# IDL.net
KiCad netlist of a schematic drawn in Altium Designer
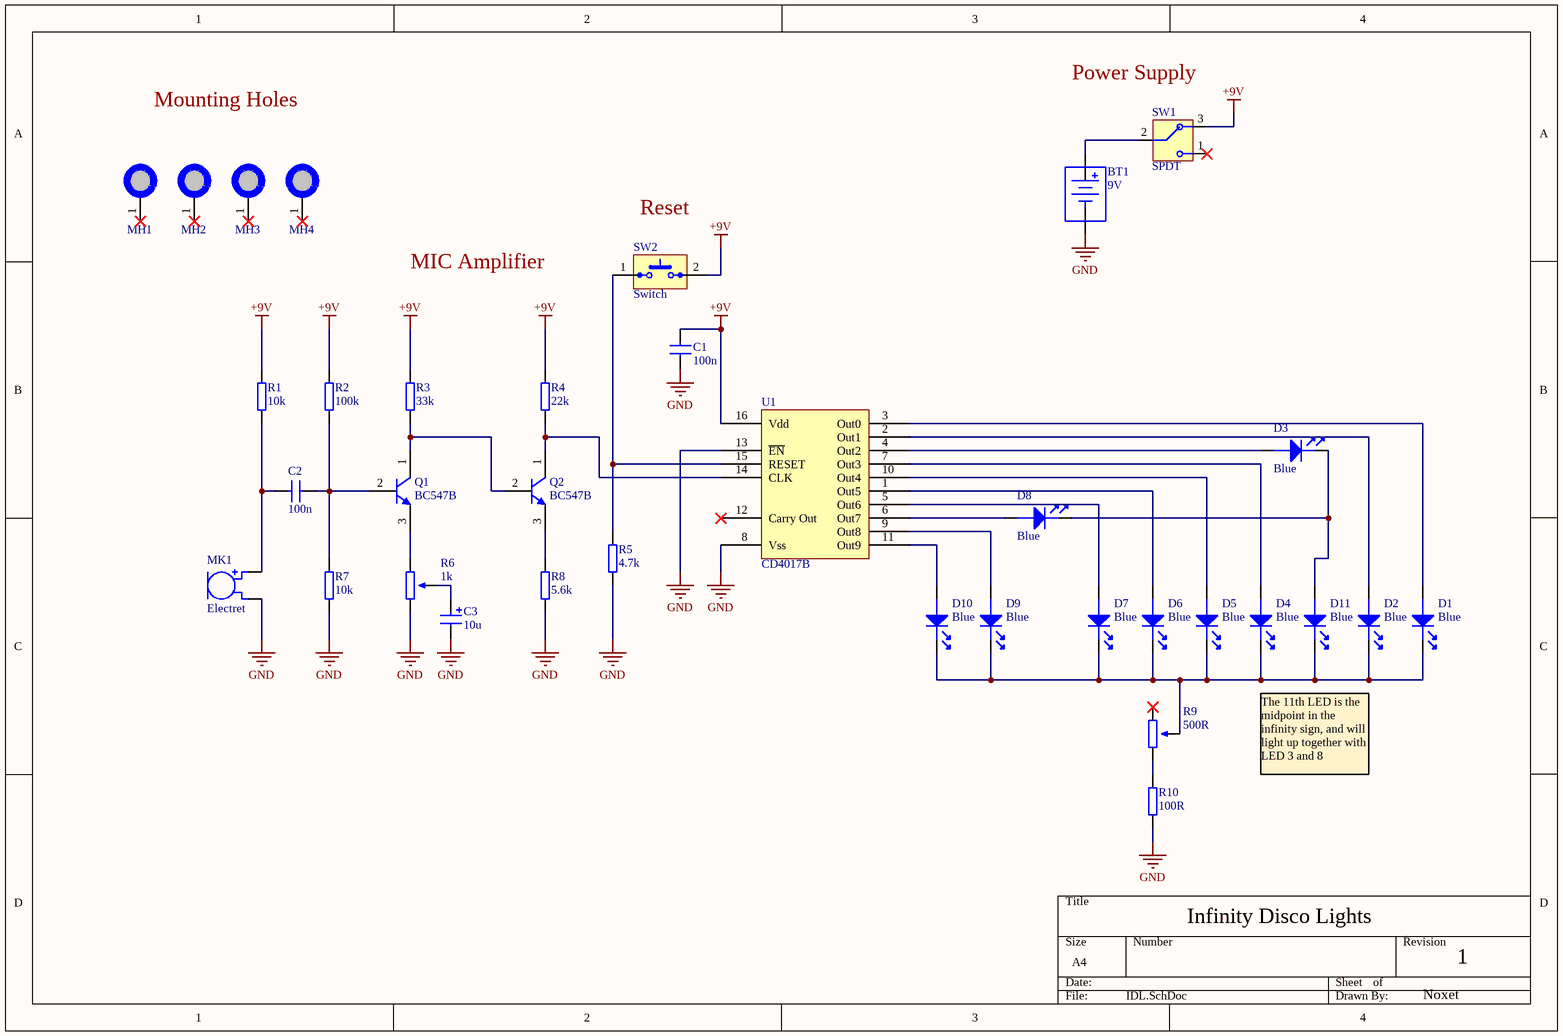
[diagram p0: IDL.SchDoc]

(export (version "E")
  (design (tool "Eeschema 10.0.6"))
  (components
    (comp (ref "BT1")
      (value "9V")
      (footprint "Battery_Holder_9V")
      (description "Electrokit art nr: 41003388")
      (libsource (lib "IDL") (part "Battery Holder 9v"))
    )
    (comp (ref "C1")
      (value "100n")
      (footprint "C_CERAMIC_TH_P5.08mm")
      (libsource (lib "IDL") (part "Cap Ceramic"))
    )
    (comp (ref "C2")
      (value "100n")
      (footprint "C_CERAMIC_TH_P5.08mm")
      (libsource (lib "IDL") (part "Cap Ceramic"))
    )
    (comp (ref "C3")
      (value "10u")
      (footprint "C_Radial_D6.3mm_H6mm_P2.5mm")
      (description "D6.3mm H6mm P2.5mm")
      (libsource (lib "IDL") (part "Cap TH Polarized"))
    )
    (comp (ref "D1") (value "Blue") (footprint "LED_Radial_10mm") (libsource (lib "IDL") (part "LED, TH")))
    (comp (ref "D2") (value "Blue") (footprint "LED_Radial_10mm") (libsource (lib "IDL") (part "LED, TH")))
    (comp (ref "D3") (value "Blue") (footprint "LED_Radial_10mm") (libsource (lib "IDL") (part "LED, TH")))
    (comp (ref "D4") (value "Blue") (footprint "LED_Radial_10mm") (libsource (lib "IDL") (part "LED, TH")))
    (comp (ref "D5") (value "Blue") (footprint "LED_Radial_10mm") (libsource (lib "IDL") (part "LED, TH")))
    (comp (ref "D6") (value "Blue") (footprint "LED_Radial_10mm") (libsource (lib "IDL") (part "LED, TH")))
    (comp (ref "D7") (value "Blue") (footprint "LED_Radial_10mm") (libsource (lib "IDL") (part "LED, TH")))
    (comp (ref "D8") (value "Blue") (footprint "LED_Radial_10mm") (libsource (lib "IDL") (part "LED, TH")))
    (comp (ref "D9") (value "Blue") (footprint "LED_Radial_10mm") (libsource (lib "IDL") (part "LED, TH")))
    (comp (ref "D10") (value "Blue") (footprint "LED_Radial_10mm") (libsource (lib "IDL") (part "LED, TH")))
    (comp (ref "D11") (value "Blue") (footprint "LED_Radial_10mm") (libsource (lib "IDL") (part "LED, TH")))
    (comp (ref "MH1")
      (value "MH_M3_NPTH")
      (footprint "MH_M3_NPTH")
      (libsource (lib "IDL") (part "MH_M3_NPTH"))
    )
    (comp (ref "MH2")
      (value "MH_M3_NPTH")
      (footprint "MH_M3_NPTH")
      (libsource (lib "IDL") (part "MH_M3_NPTH"))
    )
    (comp (ref "MH3")
      (value "MH_M3_NPTH")
      (footprint "MH_M3_NPTH")
      (libsource (lib "IDL") (part "MH_M3_NPTH"))
    )
    (comp (ref "MH4")
      (value "MH_M3_NPTH")
      (footprint "MH_M3_NPTH")
      (libsource (lib "IDL") (part "MH_M3_NPTH"))
    )
    (comp (ref "MK1")
      (value "Electret")
      (footprint "ElectretMic_9.7mm_6.7mm")
      (description "D9.7mm H6.7mm, Electrokit art nr: 40290007")
      (libsource (lib "IDL") (part "Electret Mic"))
    )
    (comp (ref "Q1")
      (value "BC547B")
      (footprint "BC547_TO-92_BENT")
      (description "BJT NPN in CBE  configuration")
      (libsource (lib "IDL") (part "BJT NPN"))
    )
    (comp (ref "Q2")
      (value "BC547B")
      (footprint "BC547_TO-92_BENT")
      (description "BJT NPN in CBE  configuration")
      (libsource (lib "IDL") (part "BJT NPN"))
    )
    (comp (ref "R1")
      (value "10k")
      (footprint "R_Axial_7.62mm")
      (description "Axial P7.62mm")
      (libsource (lib "IDL") (part "Resistor TH"))
    )
    (comp (ref "R2")
      (value "100k")
      (footprint "R_Axial_7.62mm")
      (description "Axial P7.62mm")
      (libsource (lib "IDL") (part "Resistor TH"))
    )
    (comp (ref "R3")
      (value "33k")
      (footprint "R_Axial_7.62mm")
      (description "Axial P7.62mm")
      (libsource (lib "IDL") (part "Resistor TH"))
    )
    (comp (ref "R4")
      (value "22k")
      (footprint "R_Axial_7.62mm")
      (description "Axial P7.62mm")
      (libsource (lib "IDL") (part "Resistor TH"))
    )
    (comp (ref "R5")
      (value "4.7k")
      (footprint "R_Axial_7.62mm")
      (description "Axial P7.62mm")
      (libsource (lib "IDL") (part "Resistor TH"))
    )
    (comp (ref "R6")
      (value "1k")
      (footprint "Trimpot_TH_P5.08mm")
      (description "Trimpot TH 3386P")
      (libsource (lib "IDL") (part "Pot TH"))
    )
    (comp (ref "R7")
      (value "10k")
      (footprint "R_Axial_7.62mm")
      (description "Axial P7.62mm")
      (libsource (lib "IDL") (part "Resistor TH"))
    )
    (comp (ref "R8")
      (value "5.6k")
      (footprint "R_Axial_7.62mm")
      (description "Axial P7.62mm")
      (libsource (lib "IDL") (part "Resistor TH"))
    )
    (comp (ref "R9")
      (value "500R")
      (footprint "Trimpot_TH_P5.08mm")
      (description "Trimpot TH 3386P")
      (libsource (lib "IDL") (part "Pot TH"))
    )
    (comp (ref "R10")
      (value "100R")
      (footprint "R_Axial_7.62mm")
      (description "Axial P7.62mm")
      (libsource (lib "IDL") (part "Resistor TH"))
    )
    (comp (ref "SW1")
      (value "SPDT")
      (footprint "SW_SPDT_SMTS-102-A2")
      (description "Toggle switch SPDT")
      (libsource (lib "IDL") (part "Toggle switch SPDT"))
    )
    (comp (ref "SW2")
      (value "Switch")
      (footprint "SW_Tactile_2pin_P5.08mm")
      (description "2-pin tactile button switch")
      (libsource (lib "IDL") (part "Tactile switch 2 pin"))
    )
    (comp (ref "U1")
      (value "CD4017B")
      (footprint "DIP16_W7.62mm_P2.54mm")
      (description "Decade counter")
      (libsource (lib "IDL") (part "CD4017B"))
    )
  )
  (nets
    (net (code "1") (name "+9V") (class "Default")
      (node (ref "C1") (pin "2") (pinfunction "2_2") (pintype "passive"))
      (node (ref "R1") (pin "2") (pinfunction "2_2") (pintype "passive"))
      (node (ref "R2") (pin "2") (pinfunction "2_2") (pintype "passive"))
      (node (ref "R3") (pin "2") (pinfunction "2_2") (pintype "passive"))
      (node (ref "R4") (pin "2") (pinfunction "2_2") (pintype "passive"))
      (node (ref "SW1") (pin "3") (pinfunction "3_3") (pintype "passive"))
      (node (ref "SW2") (pin "2") (pinfunction "2_2") (pintype "passive"))
      (node (ref "U1") (pin "16") (pinfunction "Vdd_16") (pintype "passive"))
    )
    (net (code "2") (name "GND") (class "Default")
      (node (ref "BT1") (pin "N") (pinfunction "NEG_N") (pintype "passive"))
      (node (ref "C1") (pin "1") (pinfunction "1_1") (pintype "passive"))
      (node (ref "C3") (pin "2") (pinfunction "2_2") (pintype "passive"))
      (node (ref "MK1") (pin "2") (pinfunction "2_2") (pintype "passive"))
      (node (ref "R10") (pin "1") (pinfunction "1_1") (pintype "passive"))
      (node (ref "R5") (pin "1") (pinfunction "1_1") (pintype "passive"))
      (node (ref "R6") (pin "1") (pinfunction "1_1") (pintype "passive"))
      (node (ref "R7") (pin "1") (pinfunction "1_1") (pintype "passive"))
      (node (ref "R8") (pin "1") (pinfunction "1_1") (pintype "passive"))
      (node (ref "U1") (pin "13") (pinfunction "~{EN}_13") (pintype "passive"))
      (node (ref "U1") (pin "8") (pinfunction "Vss_8") (pintype "passive"))
    )
    (net (code "3") (name "Net-(BT1-POS)") (class "Default")
      (node (ref "BT1") (pin "P") (pinfunction "POS_P") (pintype "passive"))
      (node (ref "SW1") (pin "2") (pinfunction "2_2") (pintype "passive"))
    )
    (net (code "4") (name "Net-(C2-Pad1)") (class "Default")
      (node (ref "C2") (pin "1") (pinfunction "1_1") (pintype "passive"))
      (node (ref "MK1") (pin "1") (pinfunction "1_1") (pintype "passive"))
      (node (ref "R1") (pin "1") (pinfunction "1_1") (pintype "passive"))
    )
    (net (code "5") (name "Net-(C3-Pad1)") (class "Default")
      (node (ref "C3") (pin "1") (pinfunction "1_1") (pintype "passive"))
      (node (ref "R6") (pin "2") (pinfunction "2_2") (pintype "passive"))
    )
    (net (code "6") (name "Net-(D1-An)") (class "Default")
      (node (ref "D1") (pin "1") (pinfunction "An_1") (pintype "passive"))
      (node (ref "U1") (pin "3") (pinfunction "Out0_3") (pintype "passive"))
    )
    (net (code "7") (name "Net-(D1-Cat)") (class "Default")
      (node (ref "D1") (pin "2") (pinfunction "Cat_2") (pintype "passive"))
      (node (ref "D10") (pin "2") (pinfunction "Cat_2") (pintype "passive"))
      (node (ref "D11") (pin "2") (pinfunction "Cat_2") (pintype "passive"))
      (node (ref "D2") (pin "2") (pinfunction "Cat_2") (pintype "passive"))
      (node (ref "D4") (pin "2") (pinfunction "Cat_2") (pintype "passive"))
      (node (ref "D5") (pin "2") (pinfunction "Cat_2") (pintype "passive"))
      (node (ref "D6") (pin "2") (pinfunction "Cat_2") (pintype "passive"))
      (node (ref "D7") (pin "2") (pinfunction "Cat_2") (pintype "passive"))
      (node (ref "D9") (pin "2") (pinfunction "Cat_2") (pintype "passive"))
      (node (ref "R9") (pin "2") (pinfunction "2_2") (pintype "passive"))
    )
    (net (code "8") (name "Net-(D2-An)") (class "Default")
      (node (ref "D2") (pin "1") (pinfunction "An_1") (pintype "passive"))
      (node (ref "U1") (pin "2") (pinfunction "Out1_2") (pintype "passive"))
    )
    (net (code "9") (name "Net-(D3-An)") (class "Default")
      (node (ref "D3") (pin "1") (pinfunction "An_1") (pintype "passive"))
      (node (ref "U1") (pin "4") (pinfunction "Out2_4") (pintype "passive"))
    )
    (net (code "10") (name "Net-(D4-An)") (class "Default")
      (node (ref "D4") (pin "1") (pinfunction "An_1") (pintype "passive"))
      (node (ref "U1") (pin "7") (pinfunction "Out3_7") (pintype "passive"))
    )
    (net (code "11") (name "Net-(D5-An)") (class "Default")
      (node (ref "D5") (pin "1") (pinfunction "An_1") (pintype "passive"))
      (node (ref "U1") (pin "10") (pinfunction "Out4_10") (pintype "passive"))
    )
    (net (code "12") (name "Net-(D6-An)") (class "Default")
      (node (ref "D6") (pin "1") (pinfunction "An_1") (pintype "passive"))
      (node (ref "U1") (pin "1") (pinfunction "Out5_1") (pintype "passive"))
    )
    (net (code "13") (name "Net-(D7-An)") (class "Default")
      (node (ref "D7") (pin "1") (pinfunction "An_1") (pintype "passive"))
      (node (ref "U1") (pin "5") (pinfunction "Out6_5") (pintype "passive"))
    )
    (net (code "14") (name "Net-(D8-An)") (class "Default")
      (node (ref "D8") (pin "1") (pinfunction "An_1") (pintype "passive"))
      (node (ref "U1") (pin "6") (pinfunction "Out7_6") (pintype "passive"))
    )
    (net (code "15") (name "Net-(D9-An)") (class "Default")
      (node (ref "D9") (pin "1") (pinfunction "An_1") (pintype "passive"))
      (node (ref "U1") (pin "9") (pinfunction "Out8_9") (pintype "passive"))
    )
    (net (code "16") (name "Net-(D10-An)") (class "Default")
      (node (ref "D10") (pin "1") (pinfunction "An_1") (pintype "passive"))
      (node (ref "U1") (pin "11") (pinfunction "Out9_11") (pintype "passive"))
    )
    (net (code "17") (name "Net-(D11-An)") (class "Default")
      (node (ref "D11") (pin "1") (pinfunction "An_1") (pintype "passive"))
      (node (ref "D3") (pin "2") (pinfunction "Cat_2") (pintype "passive"))
      (node (ref "D8") (pin "2") (pinfunction "Cat_2") (pintype "passive"))
    )
    (net (code "18") (name "Net-(Q1-B)") (class "Default")
      (node (ref "C2") (pin "2") (pinfunction "2_2") (pintype "passive"))
      (node (ref "Q1") (pin "2") (pinfunction "B_2") (pintype "passive"))
      (node (ref "R2") (pin "1") (pinfunction "1_1") (pintype "passive"))
      (node (ref "R7") (pin "2") (pinfunction "2_2") (pintype "passive"))
    )
    (net (code "19") (name "Net-(Q1-C)") (class "Default")
      (node (ref "Q1") (pin "1") (pinfunction "C_1") (pintype "passive"))
      (node (ref "Q2") (pin "2") (pinfunction "B_2") (pintype "passive"))
      (node (ref "R3") (pin "1") (pinfunction "1_1") (pintype "passive"))
    )
    (net (code "20") (name "Net-(Q1-E)") (class "Default")
      (node (ref "Q1") (pin "3") (pinfunction "E_3") (pintype "passive"))
      (node (ref "R6") (pin "3") (pinfunction "3_3") (pintype "passive"))
    )
    (net (code "21") (name "Net-(Q2-C)") (class "Default")
      (node (ref "Q2") (pin "1") (pinfunction "C_1") (pintype "passive"))
      (node (ref "R4") (pin "1") (pinfunction "1_1") (pintype "passive"))
      (node (ref "U1") (pin "14") (pinfunction "CLK_14") (pintype "passive"))
    )
    (net (code "22") (name "Net-(Q2-E)") (class "Default")
      (node (ref "Q2") (pin "3") (pinfunction "E_3") (pintype "passive"))
      (node (ref "R8") (pin "2") (pinfunction "2_2") (pintype "passive"))
    )
    (net (code "23") (name "Net-(R10-Pad2)") (class "Default")
      (node (ref "R10") (pin "2") (pinfunction "2_2") (pintype "passive"))
      (node (ref "R9") (pin "1") (pinfunction "1_1") (pintype "passive"))
    )
    (net (code "24") (name "Net-(U1-RESET)") (class "Default")
      (node (ref "R5") (pin "2") (pinfunction "2_2") (pintype "passive"))
      (node (ref "SW2") (pin "1") (pinfunction "1_1") (pintype "passive"))
      (node (ref "U1") (pin "15") (pinfunction "RESET_15") (pintype "passive"))
    )
    (net (code "25") (name "unconnected-(MH1-Pad1)") (class "Default")
      (node (ref "MH1") (pin "1") (pinfunction "1_1") (pintype "passive+no_connect"))
    )
    (net (code "26") (name "unconnected-(MH2-Pad1)") (class "Default")
      (node (ref "MH2") (pin "1") (pinfunction "1_1") (pintype "passive+no_connect"))
    )
    (net (code "27") (name "unconnected-(MH3-Pad1)") (class "Default")
      (node (ref "MH3") (pin "1") (pinfunction "1_1") (pintype "passive+no_connect"))
    )
    (net (code "28") (name "unconnected-(MH4-Pad1)") (class "Default")
      (node (ref "MH4") (pin "1") (pinfunction "1_1") (pintype "passive+no_connect"))
    )
    (net (code "29") (name "unconnected-(R9-Pad3)") (class "Default")
      (node (ref "R9") (pin "3") (pinfunction "3_3") (pintype "passive+no_connect"))
    )
    (net (code "30") (name "unconnected-(SW1-Pad1)") (class "Default")
      (node (ref "SW1") (pin "1") (pinfunction "1_1") (pintype "passive+no_connect"))
    )
    (net (code "31") (name "unconnected-(U1-Carry_Out-Pad12)") (class "Default")
      (node (ref "U1") (pin "12") (pinfunction "Carry_Out_12") (pintype "passive+no_connect"))
    )
  )
)
